# schematic.net
KiCad netlist of a schematic drawn in EAGLE
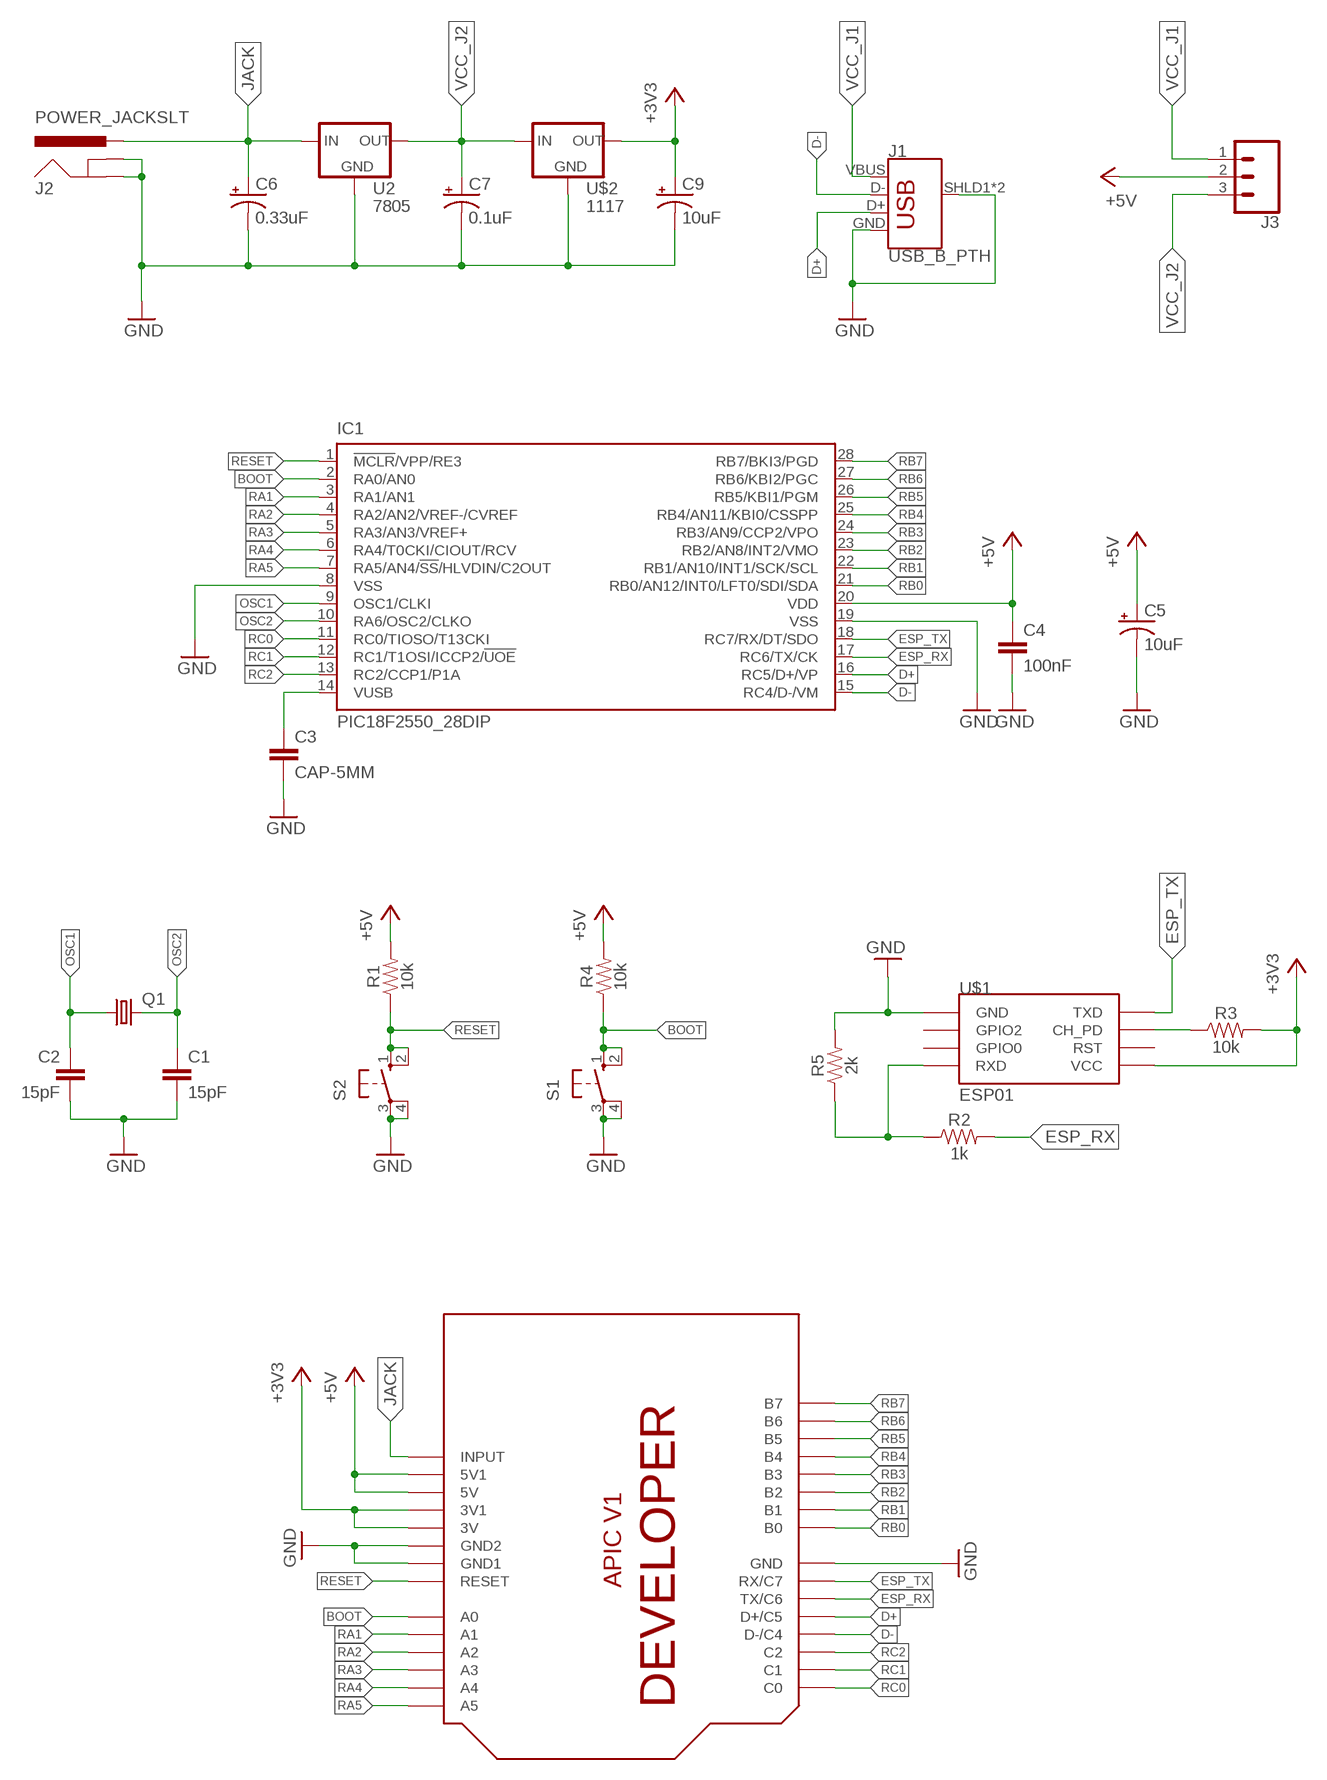
[diagram p0: schematic, sheet 1]

(export (version "E")
  (design (tool "Eeschema 10.0.6"))
  (components
    (comp (ref "C1")
      (value "15pF")
      (footprint "eagle-import:CAP-PTH-SMALL-KIT")
      (libsource (lib "eagle-import") (part "0.1UF-KIT-EZ-50V-20%"))
    )
    (comp (ref "C2")
      (value "15pF")
      (footprint "eagle-import:CAP-PTH-SMALL-KIT")
      (libsource (lib "eagle-import") (part "0.1UF-KIT-EZ-50V-20%"))
    )
    (comp (ref "C3")
      (value "CAP-5MM")
      (footprint "eagle-import:CAP-PTH-5MM")
      (libsource (lib "eagle-import") (part "CAP-5MM"))
    )
    (comp (ref "C4")
      (value "100nF")
      (footprint "eagle-import:CAP-PTH-SMALL-KIT")
      (libsource (lib "eagle-import") (part "0.1UF-KIT-EZ-50V-20%"))
    )
    (comp (ref "C5")
      (value "10uF")
      (footprint "eagle-import:CPOL-RADIAL-2.5MM-5MM")
      (libsource (lib "eagle-import") (part "10UF-POLAR-RADIAL-2.5MM-25V-20%"))
    )
    (comp (ref "C6")
      (value "0.33uF")
      (footprint "eagle-import:CPOL-RADIAL-2.5MM-5MM")
      (libsource (lib "eagle-import") (part "10UF-POLAR-RADIAL-2.5MM-25V-20%"))
    )
    (comp (ref "C7")
      (value "0.1uF")
      (footprint "eagle-import:CPOL-RADIAL-2.5MM-5MM")
      (libsource (lib "eagle-import") (part "10UF-POLAR-RADIAL-2.5MM-25V-20%"))
    )
    (comp (ref "C9")
      (value "10uF")
      (footprint "eagle-import:CPOL-RADIAL-2.5MM-5MM")
      (libsource (lib "eagle-import") (part "10UF-POLAR-RADIAL-2.5MM-25V-20%"))
    )
    (comp (ref "IC1")
      (value "PIC18F2550_28DIP")
      (footprint "eagle-import:DIL28-3")
      (fields (field (name "MF") "MICROCHIP") (field (name "MPN") "PIC18F2550-I/SP"))
      (libsource (lib "eagle-import") (part "PIC18F2_28DIP550"))
    )
    (comp (ref "J1")
      (value "USB_B_PTH")
      (footprint "eagle-import:USB-B-PTH")
      (libsource (lib "eagle-import") (part "USB_B_PTH"))
    )
    (comp (ref "J2")
      (value "POWER_JACKSLT")
      (footprint "eagle-import:POWER_JACK_SLOT")
      (libsource (lib "eagle-import") (part "POWER_JACKSLT"))
    )
    (comp (ref "J3")
      (value "CONN_03LOCK_LONGPADS")
      (footprint "eagle-import:1X03_LOCK_LONGPADS")
      (libsource (lib "eagle-import") (part "CONN_03LOCK_LONGPADS"))
    )
    (comp (ref "Q1")
      (value "CRYSTAL")
      (footprint "eagle-import:HC49U70")
      (libsource (lib "eagle-import") (part "CRYSTAL"))
    )
    (comp (ref "R1")
      (value "10k")
      (footprint "eagle-import:AXIAL-0.3")
      (libsource (lib "eagle-import") (part "10KOHM-HORIZ-1/4W-1%"))
    )
    (comp (ref "R2")
      (value "1k")
      (footprint "eagle-import:AXIAL-0.3")
      (libsource (lib "eagle-import") (part "10KOHM-HORIZ-1/4W-1%"))
    )
    (comp (ref "R3")
      (value "10k")
      (footprint "eagle-import:AXIAL-0.3")
      (libsource (lib "eagle-import") (part "10KOHM-HORIZ-1/4W-1%"))
    )
    (comp (ref "R4")
      (value "10k")
      (footprint "eagle-import:AXIAL-0.3")
      (libsource (lib "eagle-import") (part "10KOHM-HORIZ-1/4W-1%"))
    )
    (comp (ref "R5")
      (value "2k")
      (footprint "eagle-import:AXIAL-0.3")
      (libsource (lib "eagle-import") (part "10KOHM-HORIZ-1/4W-1%"))
    )
    (comp (ref "S1")
      (value "10-XX")
      (footprint "eagle-import:B3F-10XX")
      (fields (field (name "MPN") "B3F-1000"))
      (libsource (lib "eagle-import") (part "10-XX"))
    )
    (comp (ref "S2")
      (value "10-XX")
      (footprint "eagle-import:B3F-10XX")
      (fields (field (name "MPN") "B3F-1000"))
      (libsource (lib "eagle-import") (part "10-XX"))
    )
    (comp (ref "U$1")
      (value "ESP01")
      (footprint "eagle-import:ESP01")
      (libsource (lib "eagle-import") (part "ESP01"))
    )
    (comp (ref "U$2")
      (value "1117")
      (footprint "eagle-import:78XXL")
      (libsource (lib "eagle-import") (part "V_REG_LD1117VXX"))
    )
    (comp (ref "U1")
      (value "APIC-BPLACE")
      (footprint "eagle-import:APIC")
      (libsource (lib "eagle-import") (part "APIC-BPLACE"))
    )
    (comp (ref "U2")
      (value "7805")
      (footprint "eagle-import:78XXL")
      (libsource (lib "eagle-import") (part "V_REG_78XXSIDE"))
    )
  )
  (nets
    (net (code "1") (name "+3V3") (class "Default")
      (node (ref "C9") (pin "1") (pinfunction "+_1") (pintype "passive"))
      (node (ref "R3") (pin "P$2") (pinfunction "2_P$2") (pintype "passive"))
      (node (ref "U$1") (pin "VCC") (pinfunction "VCC_VCC") (pintype "bidirectional"))
      (node (ref "U$2") (pin "GND") (pinfunction "OUT_GND") (pintype "passive"))
      (node (ref "U1") (pin "3V") (pinfunction "3V_3V") (pintype "power_in"))
      (node (ref "U1") (pin "3V1") (pinfunction "3V1_3V1") (pintype "power_in"))
    )
    (net (code "2") (name "+5V") (class "Default")
      (node (ref "C4") (pin "1") (pinfunction "1_1") (pintype "passive"))
      (node (ref "C5") (pin "1") (pinfunction "+_1") (pintype "passive"))
      (node (ref "IC1") (pin "20") (pinfunction "VDD_20") (pintype "power_in"))
      (node (ref "J3") (pin "2") (pinfunction "2_2") (pintype "passive"))
      (node (ref "R1") (pin "P$2") (pinfunction "2_P$2") (pintype "passive"))
      (node (ref "R4") (pin "P$2") (pinfunction "2_P$2") (pintype "passive"))
      (node (ref "U1") (pin "5V") (pinfunction "5V_5V") (pintype "power_in"))
      (node (ref "U1") (pin "5V1") (pinfunction "5V1_5V1") (pintype "power_in"))
    )
    (net (code "3") (name "BOOT") (class "Default")
      (node (ref "IC1") (pin "2") (pinfunction "RA0/AN0_2") (pintype "bidirectional"))
      (node (ref "R4") (pin "P$1") (pinfunction "1_P$1") (pintype "passive"))
      (node (ref "S1") (pin "1") (pinfunction "S_1") (pintype "passive"))
      (node (ref "S1") (pin "2") (pinfunction "S1_2") (pintype "passive"))
      (node (ref "U1") (pin "A0") (pinfunction "A0_A0") (pintype "bidirectional"))
    )
    (net (code "4") (name "D+") (class "Default")
      (node (ref "IC1") (pin "16") (pinfunction "RC5/D+/VP_16") (pintype "bidirectional"))
      (node (ref "J1") (pin "D+") (pinfunction "D+_D+") (pintype "bidirectional"))
      (node (ref "U1") (pin "C5") (pinfunction "D+/C5_C5") (pintype "bidirectional"))
    )
    (net (code "5") (name "D-") (class "Default")
      (node (ref "IC1") (pin "15") (pinfunction "RC4/D-/VM_15") (pintype "bidirectional"))
      (node (ref "J1") (pin "D-") (pinfunction "D-_D-") (pintype "bidirectional"))
      (node (ref "U1") (pin "C4") (pinfunction "D-/C4_C4") (pintype "bidirectional"))
    )
    (net (code "6") (name "ESP_RX") (class "Default")
      (node (ref "IC1") (pin "17") (pinfunction "RC6/TX/CK_17") (pintype "bidirectional"))
      (node (ref "R2") (pin "P$2") (pinfunction "2_P$2") (pintype "passive"))
      (node (ref "U1") (pin "C6") (pinfunction "TX/C6_C6") (pintype "bidirectional"))
    )
    (net (code "7") (name "ESP_TX") (class "Default")
      (node (ref "IC1") (pin "18") (pinfunction "RC7/RX/DT/SDO_18") (pintype "bidirectional"))
      (node (ref "U$1") (pin "TX") (pinfunction "TXD_TX") (pintype "bidirectional"))
      (node (ref "U1") (pin "C7") (pinfunction "RX/C7_C7") (pintype "bidirectional"))
    )
    (net (code "8") (name "GND") (class "Default")
      (node (ref "C1") (pin "2") (pinfunction "2_2") (pintype "passive"))
      (node (ref "C2") (pin "2") (pinfunction "2_2") (pintype "passive"))
      (node (ref "C3") (pin "2") (pinfunction "2_2") (pintype "passive"))
      (node (ref "C4") (pin "2") (pinfunction "2_2") (pintype "passive"))
      (node (ref "C5") (pin "2") (pinfunction "-_2") (pintype "passive"))
      (node (ref "C6") (pin "2") (pinfunction "-_2") (pintype "passive"))
      (node (ref "C7") (pin "2") (pinfunction "-_2") (pintype "passive"))
      (node (ref "C9") (pin "2") (pinfunction "-_2") (pintype "passive"))
      (node (ref "IC1") (pin "19") (pinfunction "VSS_19") (pintype "power_in"))
      (node (ref "IC1") (pin "8") (pinfunction "VSS_8") (pintype "power_in"))
      (node (ref "J1") (pin "GND") (pinfunction "GND_GND") (pintype "power_in"))
      (node (ref "J1") (pin "SHLD1") (pinfunction "SHIELD_SHLD1") (pintype "bidirectional"))
      (node (ref "J1") (pin "SHLD2") (pinfunction "SHIELD_SHLD2") (pintype "bidirectional"))
      (node (ref "J2") (pin "GND@1") (pinfunction "GNDBREAK_GND@1") (pintype "bidirectional"))
      (node (ref "J2") (pin "GND@2") (pinfunction "GND_GND@2") (pintype "bidirectional"))
      (node (ref "R5") (pin "P$2") (pinfunction "2_P$2") (pintype "passive"))
      (node (ref "S1") (pin "3") (pinfunction "P_3") (pintype "passive"))
      (node (ref "S1") (pin "4") (pinfunction "P1_4") (pintype "passive"))
      (node (ref "S2") (pin "3") (pinfunction "P_3") (pintype "passive"))
      (node (ref "S2") (pin "4") (pinfunction "P1_4") (pintype "passive"))
      (node (ref "U$1") (pin "GND") (pinfunction "GND_GND") (pintype "bidirectional"))
      (node (ref "U$2") (pin "IN") (pinfunction "GND_IN") (pintype "input"))
      (node (ref "U1") (pin "GND") (pinfunction "GND_GND") (pintype "power_in"))
      (node (ref "U1") (pin "GND1") (pinfunction "GND1_GND1") (pintype "power_in"))
      (node (ref "U1") (pin "GND2") (pinfunction "GND2_GND2") (pintype "power_in"))
      (node (ref "U2") (pin "GND") (pinfunction "GND_GND") (pintype "input"))
    )
    (net (code "9") (name "JACK") (class "Default")
      (node (ref "C6") (pin "1") (pinfunction "+_1") (pintype "passive"))
      (node (ref "J2") (pin "PWR") (pinfunction "PWR_PWR") (pintype "bidirectional"))
      (node (ref "U1") (pin "INPUT") (pinfunction "INPUT_INPUT") (pintype "power_in"))
      (node (ref "U2") (pin "IN") (pinfunction "IN_IN") (pintype "input"))
    )
    (net (code "10") (name "Net-(IC1-VUSB)") (class "Default")
      (node (ref "C3") (pin "1") (pinfunction "1_1") (pintype "passive"))
      (node (ref "IC1") (pin "14") (pinfunction "VUSB_14") (pintype "bidirectional"))
    )
    (net (code "11") (name "Net-(R2-1)") (class "Default")
      (node (ref "R2") (pin "P$1") (pinfunction "1_P$1") (pintype "passive"))
      (node (ref "R5") (pin "P$1") (pinfunction "1_P$1") (pintype "passive"))
      (node (ref "U$1") (pin "RX") (pinfunction "RXD_RX") (pintype "bidirectional"))
    )
    (net (code "12") (name "Net-(R3-1)") (class "Default")
      (node (ref "R3") (pin "P$1") (pinfunction "1_P$1") (pintype "passive"))
      (node (ref "U$1") (pin "CH_PD") (pinfunction "CH_PD_CH_PD") (pintype "bidirectional"))
    )
    (net (code "13") (name "OSC1") (class "Default")
      (node (ref "C2") (pin "1") (pinfunction "1_1") (pintype "passive"))
      (node (ref "IC1") (pin "9") (pinfunction "OSC1/CLKI_9") (pintype "input"))
      (node (ref "Q1") (pin "1") (pinfunction "1_1") (pintype "passive"))
    )
    (net (code "14") (name "OSC2") (class "Default")
      (node (ref "C1") (pin "1") (pinfunction "1_1") (pintype "passive"))
      (node (ref "IC1") (pin "10") (pinfunction "RA6/OSC2/CLKO_10") (pintype "output"))
      (node (ref "Q1") (pin "2") (pinfunction "2_2") (pintype "passive"))
    )
    (net (code "15") (name "RA1") (class "Default")
      (node (ref "IC1") (pin "3") (pinfunction "RA1/AN1_3") (pintype "bidirectional"))
      (node (ref "U1") (pin "A1") (pinfunction "A1_A1") (pintype "bidirectional"))
    )
    (net (code "16") (name "RA2") (class "Default")
      (node (ref "IC1") (pin "4") (pinfunction "RA2/AN2/VREF-/CVREF_4") (pintype "bidirectional"))
      (node (ref "U1") (pin "A2") (pinfunction "A2_A2") (pintype "bidirectional"))
    )
    (net (code "17") (name "RA3") (class "Default")
      (node (ref "IC1") (pin "5") (pinfunction "RA3/AN3/VREF+_5") (pintype "bidirectional"))
      (node (ref "U1") (pin "A3") (pinfunction "A3_A3") (pintype "bidirectional"))
    )
    (net (code "18") (name "RA4") (class "Default")
      (node (ref "IC1") (pin "6") (pinfunction "RA4/T0CKI/CIOUT/RCV_6") (pintype "bidirectional"))
      (node (ref "U1") (pin "A4") (pinfunction "A4_A4") (pintype "bidirectional"))
    )
    (net (code "19") (name "RA5") (class "Default")
      (node (ref "IC1") (pin "7") (pinfunction "RA5/AN4/~{SS}/HLVDIN/C2OUT_7") (pintype "bidirectional"))
      (node (ref "U1") (pin "A5") (pinfunction "A5_A5") (pintype "bidirectional"))
    )
    (net (code "20") (name "RB0") (class "Default")
      (node (ref "IC1") (pin "21") (pinfunction "RB0/AN12/INT0/LFT0/SDI/SDA_21") (pintype "bidirectional"))
      (node (ref "U1") (pin "B0") (pinfunction "B0_B0") (pintype "bidirectional"))
    )
    (net (code "21") (name "RB1") (class "Default")
      (node (ref "IC1") (pin "22") (pinfunction "RB1/AN10/INT1/SCK/SCL_22") (pintype "bidirectional"))
      (node (ref "U1") (pin "B1") (pinfunction "B1_B1") (pintype "bidirectional"))
    )
    (net (code "22") (name "RB2") (class "Default")
      (node (ref "IC1") (pin "23") (pinfunction "RB2/AN8/INT2/VMO_23") (pintype "bidirectional"))
      (node (ref "U1") (pin "B2") (pinfunction "B2_B2") (pintype "bidirectional"))
    )
    (net (code "23") (name "RB3") (class "Default")
      (node (ref "IC1") (pin "24") (pinfunction "RB3/AN9/CCP2/VPO_24") (pintype "bidirectional"))
      (node (ref "U1") (pin "B3") (pinfunction "B3_B3") (pintype "bidirectional"))
    )
    (net (code "24") (name "RB4") (class "Default")
      (node (ref "IC1") (pin "25") (pinfunction "RB4/AN11/KBI0/CSSPP_25") (pintype "bidirectional"))
      (node (ref "U1") (pin "B4") (pinfunction "B4_B4") (pintype "bidirectional"))
    )
    (net (code "25") (name "RB5") (class "Default")
      (node (ref "IC1") (pin "26") (pinfunction "RB5/KBI1/PGM_26") (pintype "bidirectional"))
      (node (ref "U1") (pin "B5") (pinfunction "B5_B5") (pintype "bidirectional"))
    )
    (net (code "26") (name "RB6") (class "Default")
      (node (ref "IC1") (pin "27") (pinfunction "RB6/KBI2/PGC_27") (pintype "bidirectional"))
      (node (ref "U1") (pin "B6") (pinfunction "B6_B6") (pintype "bidirectional"))
    )
    (net (code "27") (name "RB7") (class "Default")
      (node (ref "IC1") (pin "28") (pinfunction "RB7/BKI3/PGD_28") (pintype "bidirectional"))
      (node (ref "U1") (pin "B7") (pinfunction "B7_B7") (pintype "bidirectional"))
    )
    (net (code "28") (name "RC0") (class "Default")
      (node (ref "IC1") (pin "11") (pinfunction "RC0/TIOSO/T13CKI_11") (pintype "bidirectional"))
      (node (ref "U1") (pin "C0") (pinfunction "C0_C0") (pintype "bidirectional"))
    )
    (net (code "29") (name "RC1") (class "Default")
      (node (ref "IC1") (pin "12") (pinfunction "RC1/T1OSI/ICCP2/~{UOE}_12") (pintype "bidirectional"))
      (node (ref "U1") (pin "C1") (pinfunction "C1_C1") (pintype "bidirectional"))
    )
    (net (code "30") (name "RC2") (class "Default")
      (node (ref "IC1") (pin "13") (pinfunction "RC2/CCP1/P1A_13") (pintype "bidirectional"))
      (node (ref "U1") (pin "C2") (pinfunction "C2_C2") (pintype "bidirectional"))
    )
    (net (code "31") (name "RESET") (class "Default")
      (node (ref "IC1") (pin "1") (pinfunction "~{MCLR}/VPP/RE3_1") (pintype "input"))
      (node (ref "R1") (pin "P$1") (pinfunction "1_P$1") (pintype "passive"))
      (node (ref "S2") (pin "1") (pinfunction "S_1") (pintype "passive"))
      (node (ref "S2") (pin "2") (pinfunction "S1_2") (pintype "passive"))
      (node (ref "U1") (pin "RESET") (pinfunction "RESET_RESET") (pintype "bidirectional"))
    )
    (net (code "32") (name "VCC_J1") (class "Default")
      (node (ref "J1") (pin "VBUS") (pinfunction "VBUS_VBUS") (pintype "power_in"))
      (node (ref "J3") (pin "1") (pinfunction "1_1") (pintype "passive"))
    )
    (net (code "33") (name "VCC_J2") (class "Default")
      (node (ref "C7") (pin "1") (pinfunction "+_1") (pintype "passive"))
      (node (ref "J3") (pin "3") (pinfunction "3_3") (pintype "passive"))
      (node (ref "U$2") (pin "OUT") (pinfunction "IN_OUT") (pintype "input"))
      (node (ref "U2") (pin "OUT") (pinfunction "OUT_OUT") (pintype "passive"))
    )
    (net (code "34") (name "unconnected-(U$1-PadGPIO0)") (class "Default")
      (node (ref "U$1") (pin "GPIO0") (pinfunction "GPIO0_GPIO0") (pintype "bidirectional"))
    )
    (net (code "35") (name "unconnected-(U$1-PadGPIO2)") (class "Default")
      (node (ref "U$1") (pin "GPIO2") (pinfunction "GPIO2_GPIO2") (pintype "bidirectional"))
    )
    (net (code "36") (name "unconnected-(U$1-PadRST)") (class "Default")
      (node (ref "U$1") (pin "RST") (pinfunction "RST_RST") (pintype "bidirectional"))
    )
  )
)
